# MCU.net
KiCad netlist of a schematic drawn in Altium Designer
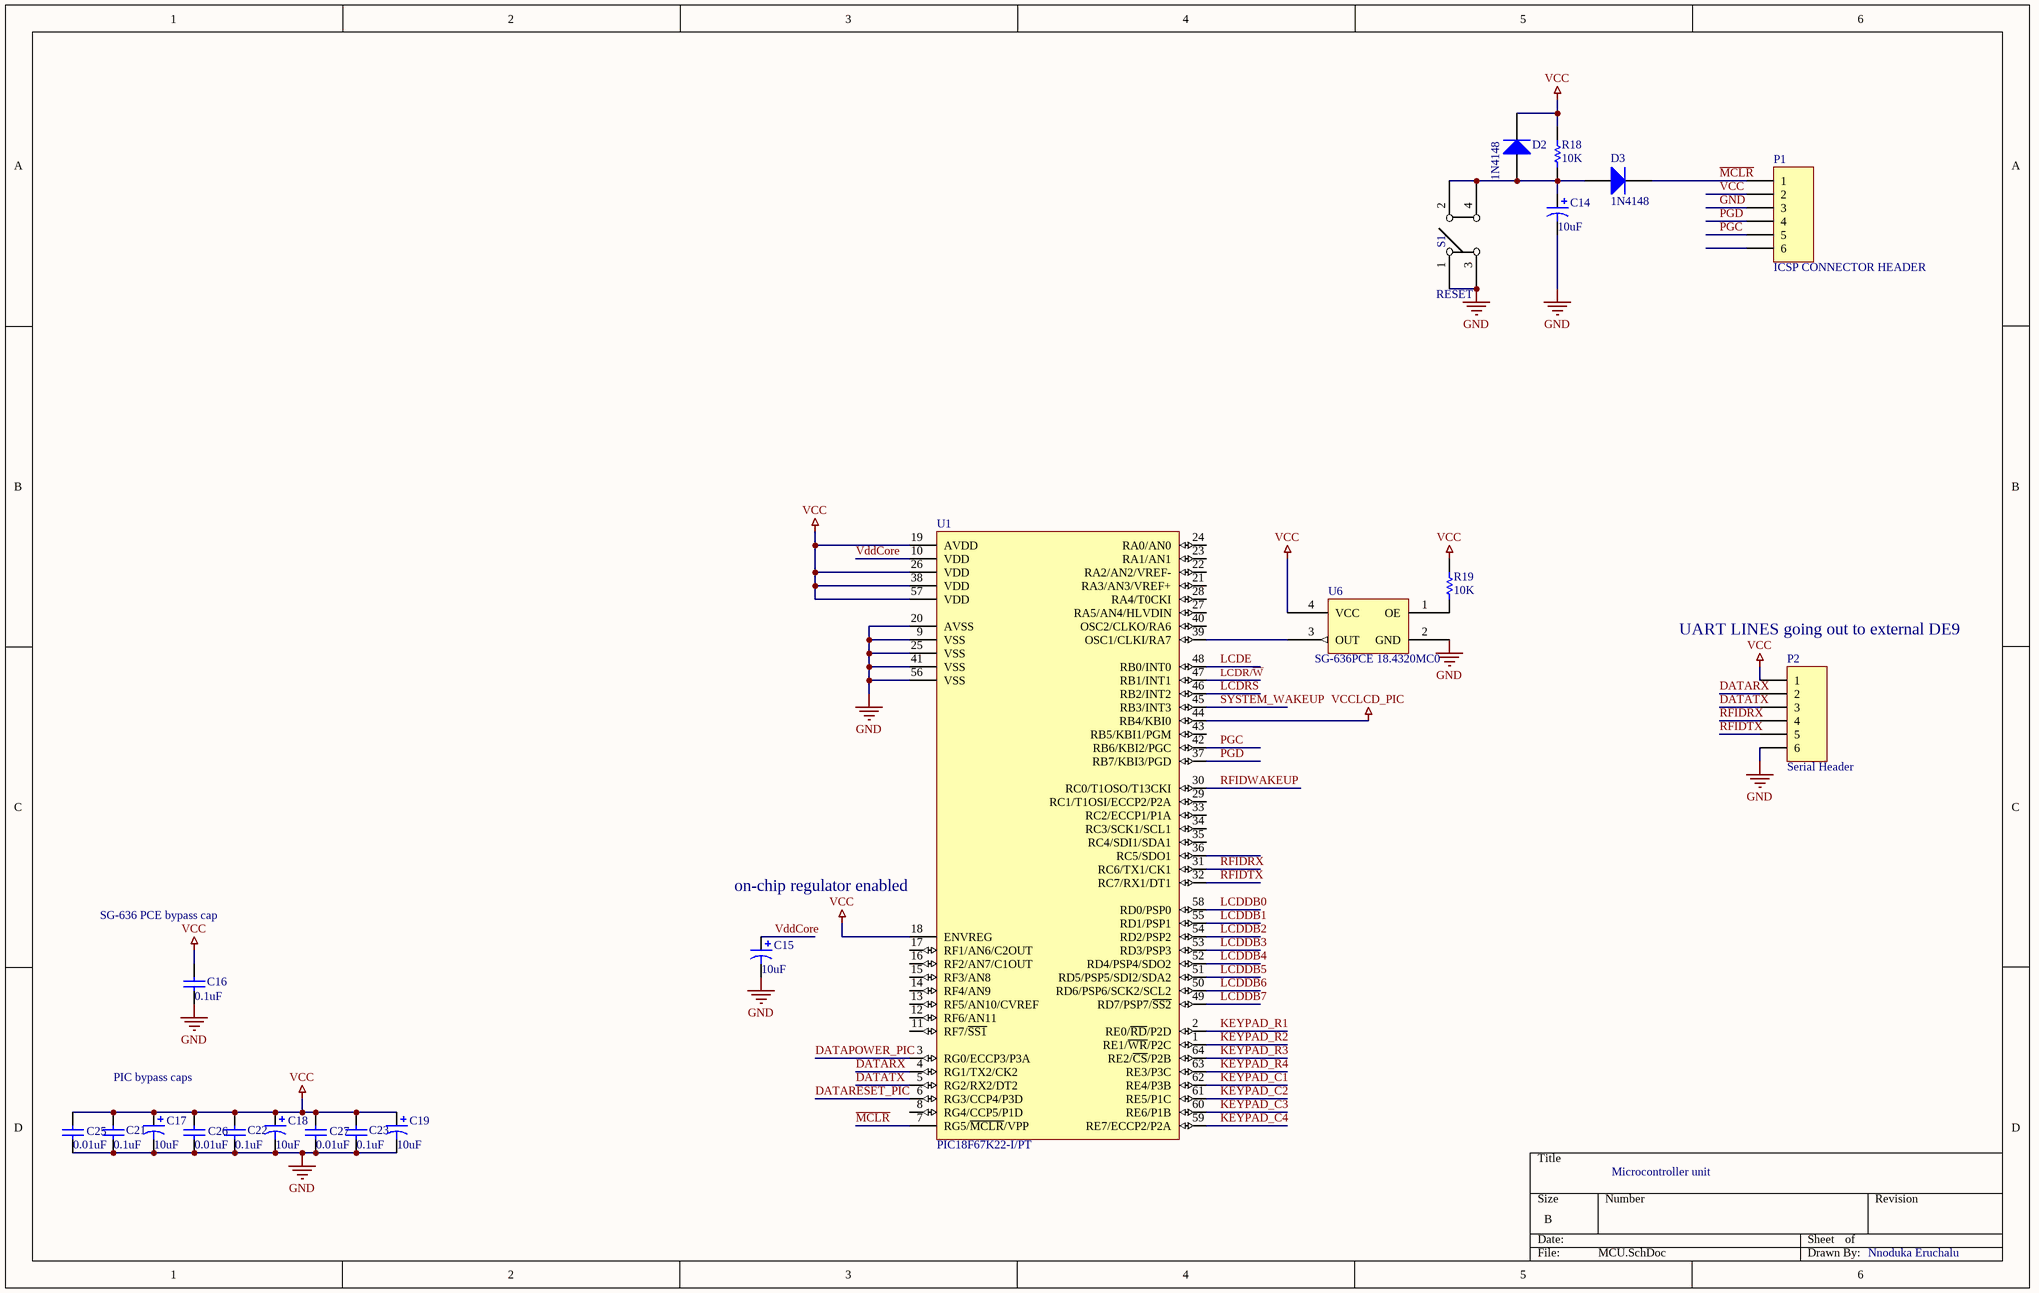
[diagram p0: MCU.SchDoc]

(export (version "E")
  (design (tool "Eeschema 10.0.6"))
  (components
    (comp (ref "C14")
      (value "10uF")
      (footprint "easypay:3216[1206]")
      (description "Polarized Capacitor (Radial)")
      (fields (field (name "Comment") "T520A106M010ATE080") (field (name "PUBLISHER") "Altium Limited"))
      (libsource (lib "Miscellaneous Devices") (part "Cap Pol1"))
    )
    (comp (ref "C15")
      (value "10uF")
      (footprint "easypay:3216[1206]")
      (description "Polarized Capacitor (Radial)")
      (fields (field (name "Comment") "T520A106M010ATE080") (field (name "PUBLISHER") "Altium Limited"))
      (libsource (lib "Miscellaneous Devices") (part "Cap Pol1"))
    )
    (comp (ref "C16")
      (value "0.1uF")
      (footprint "2012[0805]")
      (description "Ceramic Chip Capacitor - Standard")
      (fields (field (name "Comment") "C2012X7R1H104K/0.85") (field (name "PUBLISHER") "Altium Limited"))
      (libsource (lib "KEMET Chip Capacitor") (part "C0805"))
    )
    (comp (ref "C17")
      (value "10uF")
      (footprint "easypay:3216[1206]")
      (description "Polarized Capacitor (Radial)")
      (fields (field (name "Comment") "T520A106M010ATE080") (field (name "PUBLISHER") "Altium Limited"))
      (libsource (lib "Miscellaneous Devices") (part "Cap Pol1"))
    )
    (comp (ref "C18")
      (value "10uF")
      (footprint "easypay:3216[1206]")
      (description "Polarized Capacitor (Radial)")
      (fields (field (name "Comment") "T520A106M010ATE080") (field (name "PUBLISHER") "Altium Limited"))
      (libsource (lib "Miscellaneous Devices") (part "Cap Pol1"))
    )
    (comp (ref "C19")
      (value "10uF")
      (footprint "easypay:3216[1206]")
      (description "Polarized Capacitor (Radial)")
      (fields (field (name "Comment") "T520A106M010ATE080") (field (name "PUBLISHER") "Altium Limited"))
      (libsource (lib "Miscellaneous Devices") (part "Cap Pol1"))
    )
    (comp (ref "C21")
      (value "0.1uF")
      (footprint "2012[0805]")
      (description "Ceramic Chip Capacitor - Standard")
      (fields (field (name "Comment") "C2012X7R1H104K/0.85") (field (name "PUBLISHER") "Altium Limited"))
      (libsource (lib "KEMET Chip Capacitor") (part "C0805"))
    )
    (comp (ref "C22")
      (value "0.1uF")
      (footprint "2012[0805]")
      (description "Ceramic Chip Capacitor - Standard")
      (fields (field (name "Comment") "C2012X7R1H104K/0.85") (field (name "PUBLISHER") "Altium Limited"))
      (libsource (lib "KEMET Chip Capacitor") (part "C0805"))
    )
    (comp (ref "C23")
      (value "0.1uF")
      (footprint "2012[0805]")
      (description "Ceramic Chip Capacitor - Standard")
      (fields (field (name "Comment") "C2012X7R1H104K/0.85") (field (name "PUBLISHER") "Altium Limited"))
      (libsource (lib "KEMET Chip Capacitor") (part "C0805"))
    )
    (comp (ref "C25")
      (value "0.01uF")
      (footprint "2012[0805]")
      (description "Ceramic Chip Capacitor - Standard")
      (fields (field (name "Comment") "C2012X7R2E103K") (field (name "PUBLISHER") "Altium Limited"))
      (libsource (lib "KEMET Chip Capacitor") (part "C0805"))
    )
    (comp (ref "C26")
      (value "0.01uF")
      (footprint "2012[0805]")
      (description "Ceramic Chip Capacitor - Standard")
      (fields (field (name "Comment") "C2012X7R2E103K") (field (name "PUBLISHER") "Altium Limited"))
      (libsource (lib "KEMET Chip Capacitor") (part "C0805"))
    )
    (comp (ref "C27")
      (value "0.01uF")
      (footprint "2012[0805]")
      (description "Ceramic Chip Capacitor - Standard")
      (fields (field (name "Comment") "C2012X7R2E103K") (field (name "PUBLISHER") "Altium Limited"))
      (libsource (lib "KEMET Chip Capacitor") (part "C0805"))
    )
    (comp (ref "D2")
      (value "1N4148")
      (footprint "easypay:SOD123")
      (description "High Conductance Fast Diode")
      (fields (field (name "PUBLISHER") "Altium Limited"))
      (libsource (lib "Miscellaneous Devices") (part "Diode 1N4148"))
    )
    (comp (ref "D3")
      (value "1N4148")
      (footprint "easypay:SOD123")
      (description "High Conductance Fast Diode")
      (fields (field (name "PUBLISHER") "Altium Limited"))
      (libsource (lib "Miscellaneous Devices") (part "Diode 1N4148"))
    )
    (comp (ref "P1")
      (value "ICSP CONNECTOR HEADER")
      (footprint "HDR1X6")
      (description "Header, 6-Pin")
      (fields (field (name "PUBLISHER") "Altium Limited"))
      (libsource (lib "Miscellaneous Connectors") (part "Header 6"))
    )
    (comp (ref "P2")
      (value "Serial Header")
      (footprint "HDR1X6")
      (description "Header, 6-Pin")
      (fields (field (name "PUBLISHER") "Altium Limited"))
      (libsource (lib "Miscellaneous Connectors") (part "Header 6"))
    )
    (comp (ref "R18")
      (value "10K")
      (footprint "Miscellaneous Devices:2012[0805]")
      (description "Resistor")
      (fields (field (name "Comment") "ERJ-6GEYJ103V") (field (name "PUBLISHER") "Altium Limited"))
      (libsource (lib "Miscellaneous Devices") (part "Res1"))
    )
    (comp (ref "R19")
      (value "10K")
      (footprint "Miscellaneous Devices:2012[0805]")
      (description "Resistor")
      (fields (field (name "Comment") "ERJ-6GEYJ103V") (field (name "PUBLISHER") "Altium Limited"))
      (libsource (lib "Miscellaneous Devices") (part "Res1"))
    )
    (comp (ref "S1")
      (value "RESET")
      (footprint "D6C")
      (fields (field (name "Comment") "D6C00 F2 LFS"))
      (libsource (lib "easypay") (part "D6C"))
    )
    (comp (ref "U1")
      (value "PIC18F67K22-I/PT")
      (footprint "TQFP-PT64_N")
      (fields (field (name "PUBLISHER") "Altium Limited"))
      (libsource (lib "Microchip Microcontroller 8-Bit PIC18") (part "PIC18F6722-I/PT"))
    )
    (comp (ref "U6")
      (value "SG-636PCE 18.4320MC0")
      (footprint "SG-636PCE")
      (libsource (lib "easypay") (part "SG636PCE"))
    )
  )
  (nets
    (net (code "1") (name "/DATAPOWER_PIC") (class "Default")
      (node (ref "U1") (pin "3") (pinfunction "RG0/ECCP3/P3A_3") (pintype "bidirectional"))
    )
    (net (code "2") (name "/DATARESET_PIC") (class "Default")
      (node (ref "U1") (pin "6") (pinfunction "RG3/CCP4/P3D_6") (pintype "bidirectional"))
    )
    (net (code "3") (name "/DATARX") (class "Default")
      (node (ref "P2") (pin "2") (pinfunction "2_2") (pintype "passive"))
      (node (ref "U1") (pin "4") (pinfunction "RG1/TX2/CK2_4") (pintype "bidirectional"))
    )
    (net (code "4") (name "/DATATX") (class "Default")
      (node (ref "P2") (pin "3") (pinfunction "3_3") (pintype "passive"))
      (node (ref "U1") (pin "5") (pinfunction "RG2/RX2/DT2_5") (pintype "bidirectional"))
    )
    (net (code "5") (name "/KEYPAD_C1") (class "Default")
      (node (ref "U1") (pin "62") (pinfunction "RE4/P3B_62") (pintype "bidirectional"))
    )
    (net (code "6") (name "/KEYPAD_C2") (class "Default")
      (node (ref "U1") (pin "61") (pinfunction "RE5/P1C_61") (pintype "bidirectional"))
    )
    (net (code "7") (name "/KEYPAD_C3") (class "Default")
      (node (ref "U1") (pin "60") (pinfunction "RE6/P1B_60") (pintype "bidirectional"))
    )
    (net (code "8") (name "/KEYPAD_C4") (class "Default")
      (node (ref "U1") (pin "59") (pinfunction "RE7/ECCP2/P2A_59") (pintype "bidirectional"))
    )
    (net (code "9") (name "/KEYPAD_R1") (class "Default")
      (node (ref "U1") (pin "2") (pinfunction "RE0/~{RD}/P2D_2") (pintype "bidirectional"))
    )
    (net (code "10") (name "/KEYPAD_R2") (class "Default")
      (node (ref "U1") (pin "1") (pinfunction "RE1/~{WR}/P2C_1") (pintype "bidirectional"))
    )
    (net (code "11") (name "/KEYPAD_R3") (class "Default")
      (node (ref "U1") (pin "64") (pinfunction "RE2/~{CS}/P2B_64") (pintype "bidirectional"))
    )
    (net (code "12") (name "/KEYPAD_R4") (class "Default")
      (node (ref "U1") (pin "63") (pinfunction "RE3/P3C_63") (pintype "bidirectional"))
    )
    (net (code "13") (name "/LCDDB0") (class "Default")
      (node (ref "U1") (pin "58") (pinfunction "RD0/PSP0_58") (pintype "bidirectional"))
    )
    (net (code "14") (name "/LCDDB1") (class "Default")
      (node (ref "U1") (pin "55") (pinfunction "RD1/PSP1_55") (pintype "bidirectional"))
    )
    (net (code "15") (name "/LCDDB2") (class "Default")
      (node (ref "U1") (pin "54") (pinfunction "RD2/PSP2_54") (pintype "bidirectional"))
    )
    (net (code "16") (name "/LCDDB3") (class "Default")
      (node (ref "U1") (pin "53") (pinfunction "RD3/PSP3_53") (pintype "bidirectional"))
    )
    (net (code "17") (name "/LCDDB4") (class "Default")
      (node (ref "U1") (pin "52") (pinfunction "RD4/PSP4/SDO2_52") (pintype "bidirectional"))
    )
    (net (code "18") (name "/LCDDB5") (class "Default")
      (node (ref "U1") (pin "51") (pinfunction "RD5/PSP5/SDI2/SDA2_51") (pintype "bidirectional"))
    )
    (net (code "19") (name "/LCDDB6") (class "Default")
      (node (ref "U1") (pin "50") (pinfunction "RD6/PSP6/SCK2/SCL2_50") (pintype "bidirectional"))
    )
    (net (code "20") (name "/LCDDB7") (class "Default")
      (node (ref "U1") (pin "49") (pinfunction "RD7/PSP7/~{SS2}_49") (pintype "bidirectional"))
    )
    (net (code "21") (name "/LCDE") (class "Default")
      (node (ref "U1") (pin "48") (pinfunction "RB0/INT0_48") (pintype "bidirectional"))
    )
    (net (code "22") (name "/LCDRS") (class "Default")
      (node (ref "U1") (pin "46") (pinfunction "RB2/INT2_46") (pintype "bidirectional"))
    )
    (net (code "23") (name "/LCDR{slash}~{W}") (class "Default")
      (node (ref "U1") (pin "47") (pinfunction "RB1/INT1_47") (pintype "bidirectional"))
    )
    (net (code "24") (name "/PGC") (class "Default")
      (node (ref "P1") (pin "5") (pinfunction "5_5") (pintype "passive"))
      (node (ref "U1") (pin "42") (pinfunction "RB6/KBI2/PGC_42") (pintype "bidirectional"))
    )
    (net (code "25") (name "/PGD") (class "Default")
      (node (ref "P1") (pin "4") (pinfunction "4_4") (pintype "passive"))
      (node (ref "U1") (pin "37") (pinfunction "RB7/KBI3/PGD_37") (pintype "bidirectional"))
    )
    (net (code "26") (name "/RFIDRX") (class "Default")
      (node (ref "P2") (pin "4") (pinfunction "4_4") (pintype "passive"))
      (node (ref "U1") (pin "31") (pinfunction "RC6/TX1/CK1_31") (pintype "bidirectional"))
    )
    (net (code "27") (name "/RFIDTX") (class "Default")
      (node (ref "P2") (pin "5") (pinfunction "5_5") (pintype "passive"))
      (node (ref "U1") (pin "32") (pinfunction "RC7/RX1/DT1_32") (pintype "bidirectional"))
    )
    (net (code "28") (name "/RFIDWAKEUP") (class "Default")
      (node (ref "U1") (pin "30") (pinfunction "RC0/T1OSO/T13CKI_30") (pintype "bidirectional"))
    )
    (net (code "29") (name "/SYSTEM_WAKEUP") (class "Default")
      (node (ref "U1") (pin "45") (pinfunction "RB3/INT3_45") (pintype "bidirectional"))
    )
    (net (code "30") (name "/VddCore") (class "Default")
      (node (ref "C15") (pin "1") (pinfunction "1_1") (pintype "passive"))
      (node (ref "U1") (pin "10") (pinfunction "VDD_10") (pintype "power_in"))
    )
    (net (code "31") (name "/~{MCLR}") (class "Default")
      (node (ref "D3") (pin "2") (pinfunction "K_2") (pintype "passive"))
      (node (ref "P1") (pin "1") (pinfunction "1_1") (pintype "passive"))
      (node (ref "U1") (pin "7") (pinfunction "RG5/~{MCLR}/VPP_7") (pintype "passive"))
    )
    (net (code "32") (name "GND") (class "Default")
      (node (ref "C14") (pin "2") (pinfunction "2_2") (pintype "passive"))
      (node (ref "C15") (pin "2") (pinfunction "2_2") (pintype "passive"))
      (node (ref "C16") (pin "1") (pinfunction "1_1") (pintype "passive"))
      (node (ref "C17") (pin "2") (pinfunction "2_2") (pintype "passive"))
      (node (ref "C18") (pin "2") (pinfunction "2_2") (pintype "passive"))
      (node (ref "C19") (pin "2") (pinfunction "2_2") (pintype "passive"))
      (node (ref "C21") (pin "1") (pinfunction "1_1") (pintype "passive"))
      (node (ref "C22") (pin "1") (pinfunction "1_1") (pintype "passive"))
      (node (ref "C23") (pin "1") (pinfunction "1_1") (pintype "passive"))
      (node (ref "C25") (pin "1") (pinfunction "1_1") (pintype "passive"))
      (node (ref "C26") (pin "1") (pinfunction "1_1") (pintype "passive"))
      (node (ref "C27") (pin "1") (pinfunction "1_1") (pintype "passive"))
      (node (ref "P1") (pin "3") (pinfunction "3_3") (pintype "passive"))
      (node (ref "P2") (pin "6") (pinfunction "6_6") (pintype "passive"))
      (node (ref "S1") (pin "1") (pintype "passive"))
      (node (ref "S1") (pin "3") (pintype "passive"))
      (node (ref "U1") (pin "20") (pinfunction "AVSS_20") (pintype "power_in"))
      (node (ref "U1") (pin "25") (pinfunction "VSS_25") (pintype "power_in"))
      (node (ref "U1") (pin "41") (pinfunction "VSS_41") (pintype "power_in"))
      (node (ref "U1") (pin "56") (pinfunction "VSS_56") (pintype "power_in"))
      (node (ref "U1") (pin "9") (pinfunction "VSS_9") (pintype "power_in"))
      (node (ref "U6") (pin "2") (pinfunction "GND_2") (pintype "power_in"))
    )
    (net (code "33") (name "Net-(D2-A)") (class "Default")
      (node (ref "C14") (pin "1") (pinfunction "1_1") (pintype "passive"))
      (node (ref "D2") (pin "1") (pinfunction "A_1") (pintype "passive"))
      (node (ref "D3") (pin "1") (pinfunction "A_1") (pintype "passive"))
      (node (ref "R18") (pin "2") (pinfunction "2_2") (pintype "passive"))
      (node (ref "S1") (pin "2") (pintype "passive"))
      (node (ref "S1") (pin "4") (pintype "passive"))
    )
    (net (code "34") (name "Net-(U1-OSC1{slash}CLKI{slash}RA7)") (class "Default")
      (node (ref "U1") (pin "39") (pinfunction "OSC1/CLKI/RA7_39") (pintype "bidirectional"))
      (node (ref "U6") (pin "3") (pinfunction "OUT_3") (pintype "output"))
    )
    (net (code "35") (name "Net-(U6-OE)") (class "Default")
      (node (ref "R19") (pin "2") (pinfunction "2_2") (pintype "passive"))
      (node (ref "U6") (pin "1") (pinfunction "OE_1") (pintype "passive"))
    )
    (net (code "36") (name "VCC") (class "Default")
      (node (ref "C16") (pin "2") (pinfunction "2_2") (pintype "passive"))
      (node (ref "C17") (pin "1") (pinfunction "1_1") (pintype "passive"))
      (node (ref "C18") (pin "1") (pinfunction "1_1") (pintype "passive"))
      (node (ref "C19") (pin "1") (pinfunction "1_1") (pintype "passive"))
      (node (ref "C21") (pin "2") (pinfunction "2_2") (pintype "passive"))
      (node (ref "C22") (pin "2") (pinfunction "2_2") (pintype "passive"))
      (node (ref "C23") (pin "2") (pinfunction "2_2") (pintype "passive"))
      (node (ref "C25") (pin "2") (pinfunction "2_2") (pintype "passive"))
      (node (ref "C26") (pin "2") (pinfunction "2_2") (pintype "passive"))
      (node (ref "C27") (pin "2") (pinfunction "2_2") (pintype "passive"))
      (node (ref "D2") (pin "2") (pinfunction "K_2") (pintype "passive"))
      (node (ref "P1") (pin "2") (pinfunction "2_2") (pintype "passive"))
      (node (ref "P2") (pin "1") (pinfunction "1_1") (pintype "passive"))
      (node (ref "R18") (pin "1") (pinfunction "1_1") (pintype "passive"))
      (node (ref "R19") (pin "1") (pinfunction "1_1") (pintype "passive"))
      (node (ref "U1") (pin "18") (pinfunction "ENVREG_18") (pintype "power_in"))
      (node (ref "U1") (pin "19") (pinfunction "AVDD_19") (pintype "power_in"))
      (node (ref "U1") (pin "26") (pinfunction "VDD_26") (pintype "power_in"))
      (node (ref "U1") (pin "38") (pinfunction "VDD_38") (pintype "power_in"))
      (node (ref "U1") (pin "57") (pinfunction "VDD_57") (pintype "power_in"))
      (node (ref "U6") (pin "4") (pinfunction "VCC_4") (pintype "power_in"))
    )
    (net (code "37") (name "VCCLCD_PIC") (class "Default")
      (node (ref "U1") (pin "44") (pinfunction "RB4/KBI0_44") (pintype "bidirectional"))
    )
    (net (code "38") (name "unconnected-(P1-Pad6)") (class "Default")
      (node (ref "P1") (pin "6") (pinfunction "6_6") (pintype "passive"))
    )
    (net (code "39") (name "unconnected-(U1-OSC2{slash}CLKO{slash}RA6-Pad40)") (class "Default")
      (node (ref "U1") (pin "40") (pinfunction "OSC2/CLKO/RA6_40") (pintype "bidirectional"))
    )
    (net (code "40") (name "unconnected-(U1-RA0{slash}AN0-Pad24)") (class "Default")
      (node (ref "U1") (pin "24") (pinfunction "RA0/AN0_24") (pintype "bidirectional"))
    )
    (net (code "41") (name "unconnected-(U1-RA1{slash}AN1-Pad23)") (class "Default")
      (node (ref "U1") (pin "23") (pinfunction "RA1/AN1_23") (pintype "bidirectional"))
    )
    (net (code "42") (name "unconnected-(U1-RA2{slash}AN2{slash}VREF--Pad22)") (class "Default")
      (node (ref "U1") (pin "22") (pinfunction "RA2/AN2/VREF-_22") (pintype "bidirectional"))
    )
    (net (code "43") (name "unconnected-(U1-RA3{slash}AN3{slash}VREF+-Pad21)") (class "Default")
      (node (ref "U1") (pin "21") (pinfunction "RA3/AN3/VREF+_21") (pintype "bidirectional"))
    )
    (net (code "44") (name "unconnected-(U1-RA4{slash}T0CKI-Pad28)") (class "Default")
      (node (ref "U1") (pin "28") (pinfunction "RA4/T0CKI_28") (pintype "bidirectional"))
    )
    (net (code "45") (name "unconnected-(U1-RA5{slash}AN4{slash}HLVDIN-Pad27)") (class "Default")
      (node (ref "U1") (pin "27") (pinfunction "RA5/AN4/HLVDIN_27") (pintype "bidirectional"))
    )
    (net (code "46") (name "unconnected-(U1-RB5{slash}KBI1{slash}PGM-Pad43)") (class "Default")
      (node (ref "U1") (pin "43") (pinfunction "RB5/KBI1/PGM_43") (pintype "bidirectional"))
    )
    (net (code "47") (name "unconnected-(U1-RC1{slash}T1OSI{slash}ECCP2{slash}P2A-Pad29)") (class "Default")
      (node (ref "U1") (pin "29") (pinfunction "RC1/T1OSI/ECCP2/P2A_29") (pintype "bidirectional"))
    )
    (net (code "48") (name "unconnected-(U1-RC2{slash}ECCP1{slash}P1A-Pad33)") (class "Default")
      (node (ref "U1") (pin "33") (pinfunction "RC2/ECCP1/P1A_33") (pintype "bidirectional"))
    )
    (net (code "49") (name "unconnected-(U1-RC3{slash}SCK1{slash}SCL1-Pad34)") (class "Default")
      (node (ref "U1") (pin "34") (pinfunction "RC3/SCK1/SCL1_34") (pintype "bidirectional"))
    )
    (net (code "50") (name "unconnected-(U1-RC4{slash}SDI1{slash}SDA1-Pad35)") (class "Default")
      (node (ref "U1") (pin "35") (pinfunction "RC4/SDI1/SDA1_35") (pintype "bidirectional"))
    )
    (net (code "51") (name "unconnected-(U1-RC5{slash}SDO1-Pad36)") (class "Default")
      (node (ref "U1") (pin "36") (pinfunction "RC5/SDO1_36") (pintype "bidirectional"))
    )
    (net (code "52") (name "unconnected-(U1-RF1{slash}AN6{slash}C2OUT-Pad17)") (class "Default")
      (node (ref "U1") (pin "17") (pinfunction "RF1/AN6/C2OUT_17") (pintype "bidirectional"))
    )
    (net (code "53") (name "unconnected-(U1-RF2{slash}AN7{slash}C1OUT-Pad16)") (class "Default")
      (node (ref "U1") (pin "16") (pinfunction "RF2/AN7/C1OUT_16") (pintype "bidirectional"))
    )
    (net (code "54") (name "unconnected-(U1-RF3{slash}AN8-Pad15)") (class "Default")
      (node (ref "U1") (pin "15") (pinfunction "RF3/AN8_15") (pintype "bidirectional"))
    )
    (net (code "55") (name "unconnected-(U1-RF4{slash}AN9-Pad14)") (class "Default")
      (node (ref "U1") (pin "14") (pinfunction "RF4/AN9_14") (pintype "bidirectional"))
    )
    (net (code "56") (name "unconnected-(U1-RF5{slash}AN10{slash}CVREF-Pad13)") (class "Default")
      (node (ref "U1") (pin "13") (pinfunction "RF5/AN10/CVREF_13") (pintype "bidirectional"))
    )
    (net (code "57") (name "unconnected-(U1-RF6{slash}AN11-Pad12)") (class "Default")
      (node (ref "U1") (pin "12") (pinfunction "RF6/AN11_12") (pintype "bidirectional"))
    )
    (net (code "58") (name "unconnected-(U1-RF7{slash}~{SS1}-Pad11)") (class "Default")
      (node (ref "U1") (pin "11") (pinfunction "RF7/~{SS1}_11") (pintype "bidirectional"))
    )
    (net (code "59") (name "unconnected-(U1-RG4{slash}CCP5{slash}P1D-Pad8)") (class "Default")
      (node (ref "U1") (pin "8") (pinfunction "RG4/CCP5/P1D_8") (pintype "bidirectional"))
    )
  )
)
